# LB_BIT_oX_1IN_1OUT-LARGE-v03_1_1x.net
KiCad netlist of a schematic drawn in EAGLE
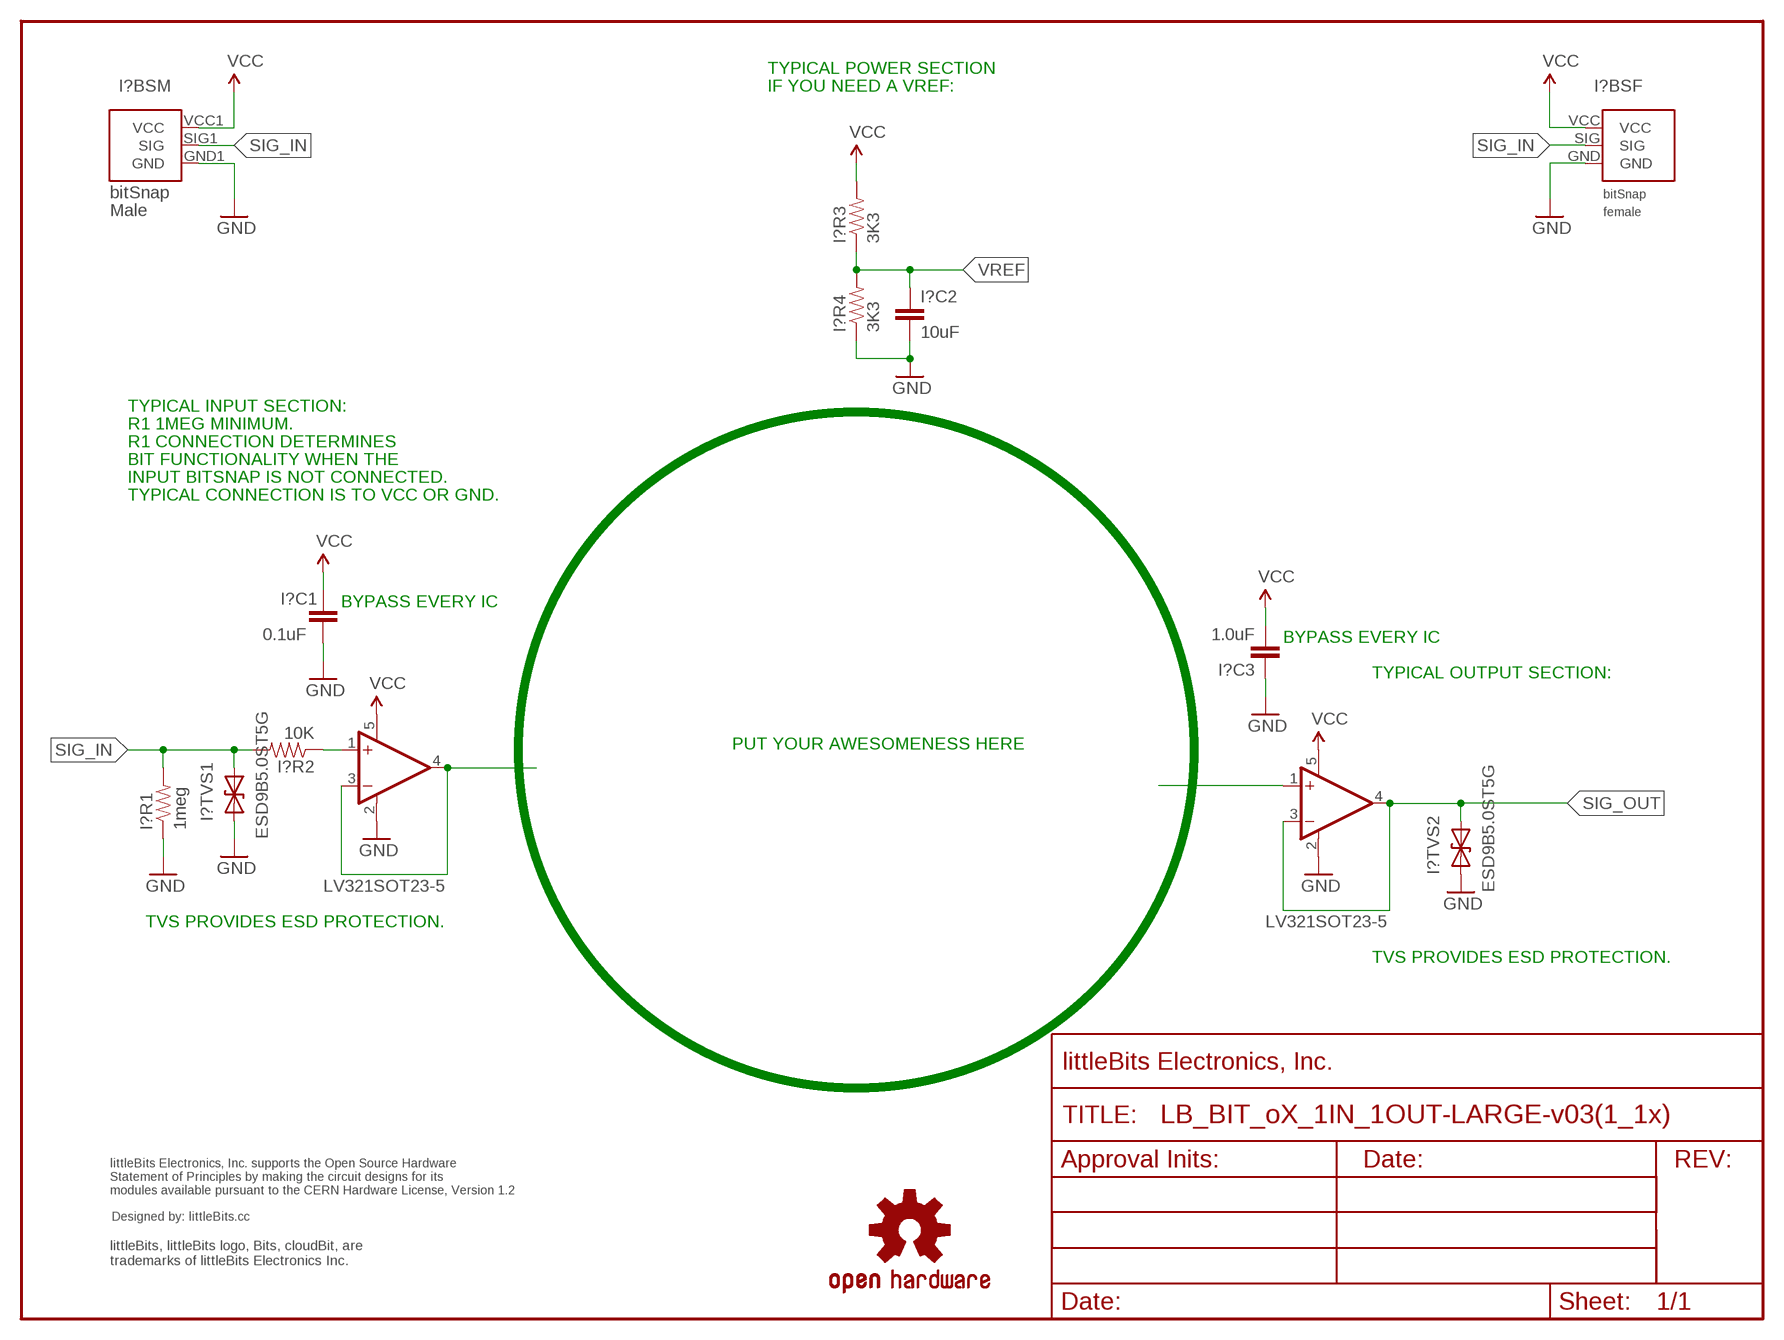
[diagram p0: schematic, sheet 1]

(export (version "E")
  (design (tool "Eeschema 10.0.6"))
  (components
    (comp (ref "I?BSF")
      (value "BITSNAP_V03_FEMALE")
      (footprint "eagle-import:BITSNAP_V03_FEMALE")
      (libsource (lib "eagle-import") (part "BITSNAP_V03_FEMALE"))
    )
    (comp (ref "I?BSM")
      (value "BITSNAP_V03_MALE")
      (footprint "eagle-import:BITSNAP_V03_MALE")
      (libsource (lib "eagle-import") (part "BITSNAP_V03_MALE"))
    )
    (comp (ref "I?C1")
      (value "0.1uF")
      (footprint "eagle-import:CAP-0603")
      (libsource (lib "eagle-import") (part "CAPCAP-0603"))
    )
    (comp (ref "I?C2")
      (value "10uF")
      (footprint "eagle-import:CAP-0603")
      (libsource (lib "eagle-import") (part "CAPCAP-0603"))
    )
    (comp (ref "I?C3")
      (value "1.0uF")
      (footprint "eagle-import:CAP-0603")
      (libsource (lib "eagle-import") (part "CAPCAP-0603"))
    )
    (comp (ref "I?R1")
      (value "1meg")
      (footprint "eagle-import:RES-0603")
      (libsource (lib "eagle-import") (part "RESISTOR0603"))
    )
    (comp (ref "I?R2")
      (value "10K")
      (footprint "eagle-import:RES-0603")
      (libsource (lib "eagle-import") (part "RESISTOR0603"))
    )
    (comp (ref "I?R3")
      (value "3K3")
      (footprint "eagle-import:RES-0603")
      (libsource (lib "eagle-import") (part "RESISTOR0603"))
    )
    (comp (ref "I?R4")
      (value "3K3")
      (footprint "eagle-import:RES-0603")
      (libsource (lib "eagle-import") (part "RESISTOR0603"))
    )
    (comp (ref "I?TVS1")
      (value "ESD9B5.0ST5G")
      (footprint "eagle-import:SOD-923")
      (libsource (lib "eagle-import") (part "DIODE-TVSSOD-923"))
    )
    (comp (ref "I?TVS2")
      (value "ESD9B5.0ST5G")
      (footprint "eagle-import:SOD-923")
      (libsource (lib "eagle-import") (part "DIODE-TVSSOD-923"))
    )
    (comp (ref "U$1")
      (value "OSHWCREDIT")
      (footprint "eagle-import:OSHWCREDIT")
      (libsource (lib "eagle-import") (part "OSHWCREDIT"))
    )
    (comp (ref "U$2")
      (value "FRAME-LETTER")
      (footprint "eagle-import:FABDWG01-OHW")
      (libsource (lib "eagle-import") (part "FRAME-LETTER"))
    )
    (comp (ref "U$3")
      (value "OSHW-LOGOL")
      (footprint "eagle-import:OSHW-LOGO-L")
      (libsource (lib "eagle-import") (part "OSHW-LOGOL"))
    )
    (comp (ref "U1")
      (value "LV321SOT23-5")
      (footprint "eagle-import:SOT23-5")
      (libsource (lib "eagle-import") (part "LV321SOT23-5"))
    )
    (comp (ref "U2")
      (value "LV321SOT23-5")
      (footprint "eagle-import:SOT23-5")
      (libsource (lib "eagle-import") (part "LV321SOT23-5"))
    )
  )
  (nets
    (net (code "1") (name "GND") (class "Default")
      (node (ref "I?BSF") (pin "GND") (pinfunction "GND_GND") (pintype "bidirectional"))
      (node (ref "I?BSM") (pin "GND1") (pinfunction "GND_GND1") (pintype "bidirectional"))
      (node (ref "I?C1") (pin "2") (pinfunction "2_2") (pintype "passive"))
      (node (ref "I?C2") (pin "2") (pinfunction "2_2") (pintype "passive"))
      (node (ref "I?C3") (pin "1") (pinfunction "1_1") (pintype "passive"))
      (node (ref "I?R1") (pin "1") (pinfunction "1_1") (pintype "passive"))
      (node (ref "I?R4") (pin "1") (pinfunction "1_1") (pintype "passive"))
      (node (ref "I?TVS1") (pin "1") (pinfunction "A_1") (pintype "passive"))
      (node (ref "I?TVS2") (pin "1") (pinfunction "A_1") (pintype "passive"))
      (node (ref "U1") (pin "2") (pinfunction "V-_2") (pintype "power_in"))
      (node (ref "U2") (pin "2") (pinfunction "V-_2") (pintype "power_in"))
    )
    (net (code "2") (name "Net-(U1-+IN)") (class "Default")
      (node (ref "I?R2") (pin "1") (pinfunction "1_1") (pintype "passive"))
      (node (ref "U1") (pin "1") (pinfunction "+IN_1") (pintype "input"))
    )
    (net (code "3") (name "Net-(U1--IN)") (class "Default")
      (node (ref "U1") (pin "3") (pinfunction "-IN_3") (pintype "input"))
      (node (ref "U1") (pin "4") (pinfunction "OUT_4") (pintype "output"))
    )
    (net (code "4") (name "SIG_IN") (class "Default")
      (node (ref "I?BSF") (pin "SIG") (pinfunction "SIG_SIG") (pintype "bidirectional"))
      (node (ref "I?BSM") (pin "SIG1") (pinfunction "SIG_SIG1") (pintype "bidirectional"))
      (node (ref "I?R1") (pin "2") (pinfunction "2_2") (pintype "passive"))
      (node (ref "I?R2") (pin "2") (pinfunction "2_2") (pintype "passive"))
      (node (ref "I?TVS1") (pin "2") (pinfunction "C_2") (pintype "passive"))
    )
    (net (code "5") (name "SIG_OUT") (class "Default")
      (node (ref "I?TVS2") (pin "2") (pinfunction "C_2") (pintype "passive"))
      (node (ref "U2") (pin "3") (pinfunction "-IN_3") (pintype "input"))
      (node (ref "U2") (pin "4") (pinfunction "OUT_4") (pintype "output"))
    )
    (net (code "6") (name "VCC") (class "Default")
      (node (ref "I?BSF") (pin "VCC") (pinfunction "VCC_VCC") (pintype "bidirectional"))
      (node (ref "I?BSM") (pin "VCC1") (pinfunction "VCC_VCC1") (pintype "bidirectional"))
      (node (ref "I?C1") (pin "1") (pinfunction "1_1") (pintype "passive"))
      (node (ref "I?C3") (pin "2") (pinfunction "2_2") (pintype "passive"))
      (node (ref "I?R3") (pin "2") (pinfunction "2_2") (pintype "passive"))
      (node (ref "U1") (pin "5") (pinfunction "V+_5") (pintype "power_in"))
      (node (ref "U2") (pin "5") (pinfunction "V+_5") (pintype "power_in"))
    )
    (net (code "7") (name "VREF") (class "Default")
      (node (ref "I?C2") (pin "1") (pinfunction "1_1") (pintype "passive"))
      (node (ref "I?R3") (pin "1") (pinfunction "1_1") (pintype "passive"))
      (node (ref "I?R4") (pin "2") (pinfunction "2_2") (pintype "passive"))
    )
    (net (code "8") (name "unconnected-(U2-+IN-Pad1)") (class "Default")
      (node (ref "U2") (pin "1") (pinfunction "+IN_1") (pintype "input"))
    )
  )
)
